# CAN.net
KiCad netlist of a schematic drawn in Altium Designer
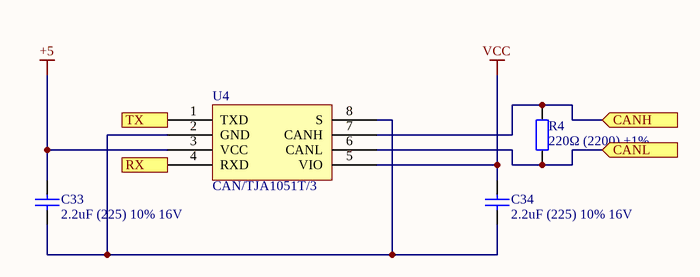
[diagram p0: CAN.SchDoc]

(export (version "E")
  (design (tool "Eeschema 10.0.6"))
  (components
    (comp (ref "C33")
      (value "2.2uF (225) 10% 16V")
      (footprint "0603_C")
      (description "贴片电容")
      (libsource (lib "Miscellaneous Devices LC") (part "0603 2.2uF (225) 10% 16V"))
    )
    (comp (ref "C34")
      (value "2.2uF (225) 10% 16V")
      (footprint "0603_C")
      (description "贴片电容")
      (libsource (lib "Miscellaneous Devices LC") (part "0603 2.2uF (225) 10% 16V"))
    )
    (comp (ref "R4")
      (value "220Ω (2200) ±1%")
      (footprint "0603_R")
      (description "贴片电阻")
      (libsource (lib "Miscellaneous Devices LC") (part "0603 220Ω (2200) 1%"))
    )
    (comp (ref "U4")
      (value "CAN/TJA1051T/3")
      (footprint "SOIC-8_150mil")
      (description "CAN")
      (libsource (lib "Miscellaneous Devices LC") (part "CAN/TJA1051T/3_[C38695]"))
    )
  )
  (nets
    (net (code "1") (name "+5") (class "Default")
      (node (ref "C33") (pin "2") (pinfunction "2_2") (pintype "passive"))
      (node (ref "U4") (pin "3") (pinfunction "VCC_3") (pintype "passive"))
    )
    (net (code "2") (name "/CANH") (class "Default")
      (node (ref "R4") (pin "2") (pinfunction "2_2") (pintype "passive"))
      (node (ref "U4") (pin "7") (pinfunction "CANH_7") (pintype "passive"))
    )
    (net (code "3") (name "/CANL") (class "Default")
      (node (ref "R4") (pin "1") (pinfunction "1_1") (pintype "passive"))
      (node (ref "U4") (pin "6") (pinfunction "CANL_6") (pintype "passive"))
    )
    (net (code "4") (name "/RX") (class "Default")
      (node (ref "U4") (pin "4") (pinfunction "RXD_4") (pintype "passive"))
    )
    (net (code "5") (name "/TX") (class "Default")
      (node (ref "U4") (pin "1") (pinfunction "TXD_1") (pintype "passive"))
    )
    (net (code "6") (name "Net-(U4-GND)") (class "Default")
      (node (ref "C33") (pin "1") (pinfunction "1_1") (pintype "passive"))
      (node (ref "C34") (pin "1") (pinfunction "1_1") (pintype "passive"))
      (node (ref "U4") (pin "2") (pinfunction "GND_2") (pintype "passive"))
      (node (ref "U4") (pin "8") (pinfunction "S_8") (pintype "passive"))
    )
    (net (code "7") (name "VCC") (class "Default")
      (node (ref "C34") (pin "2") (pinfunction "2_2") (pintype "passive"))
      (node (ref "U4") (pin "5") (pinfunction "VIO_5") (pintype "passive"))
    )
  )
)
